# POWER_GEN.net
KiCad netlist of a schematic drawn in Altium Designer
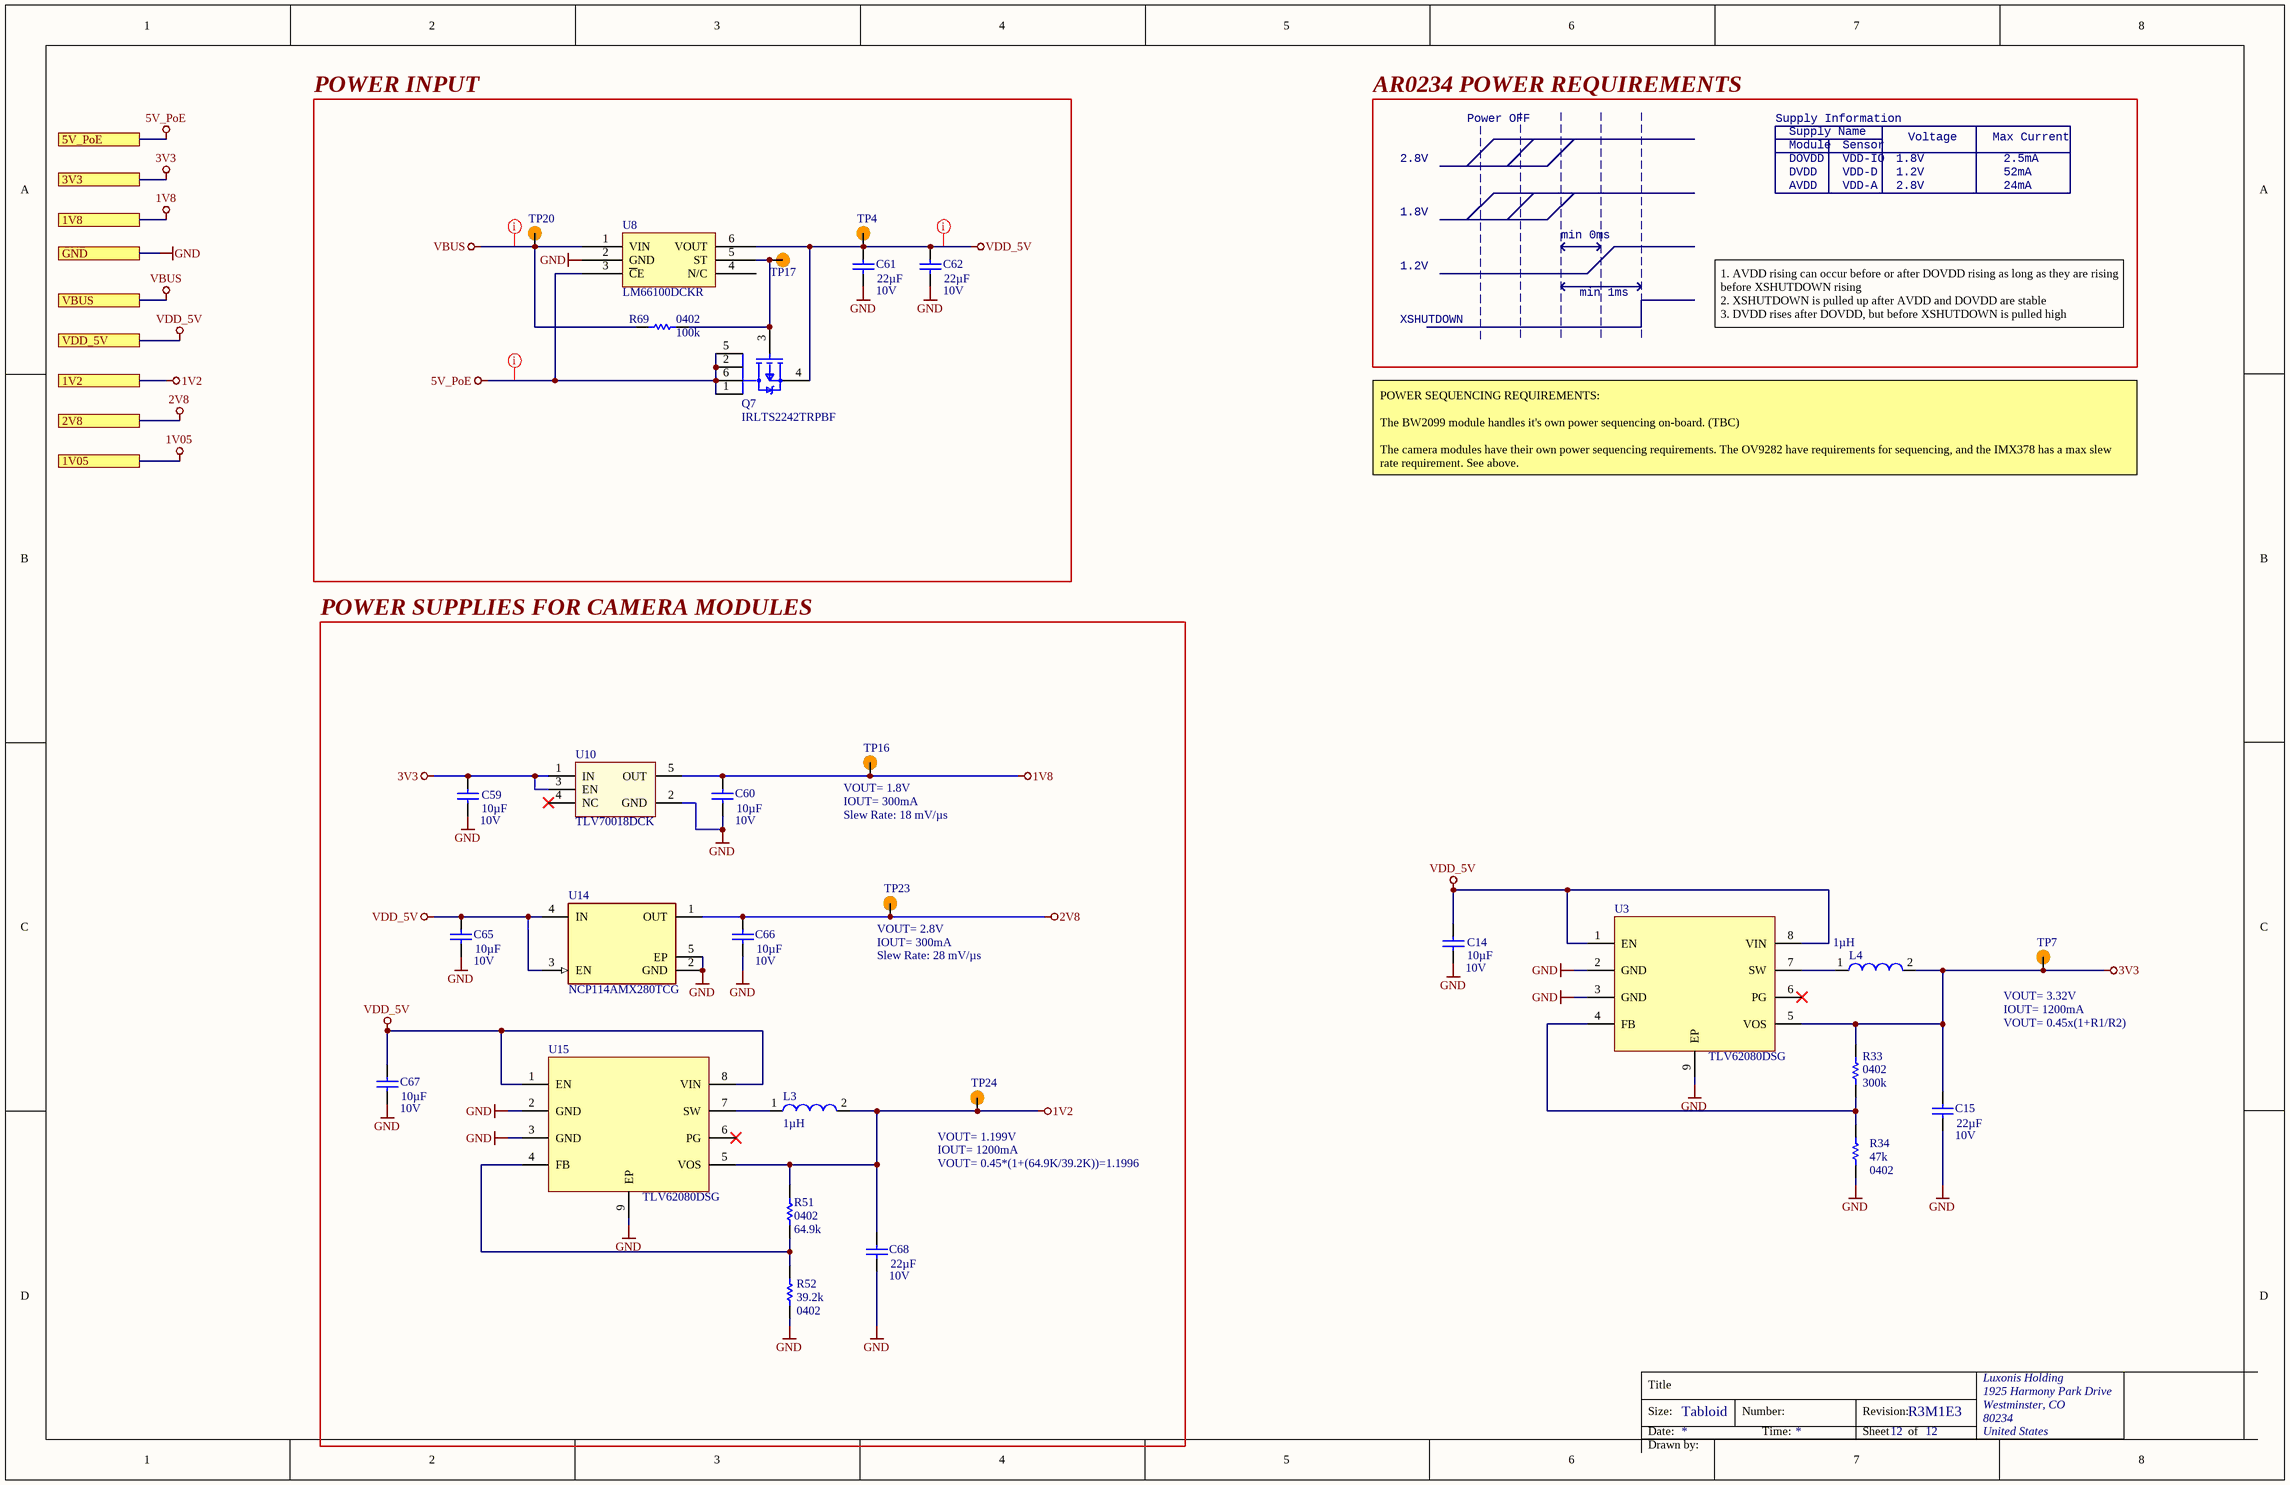
[diagram p0: POWER_GEN.SchDoc]

(export (version "E")
  (design (tool "Eeschema 10.0.6"))
  (components
    (comp (ref "C14")
      (value "10µF")
      (footprint "CAPC0603(1608)100_L")
      (description "CAP CER 10UF 10V X5R 0603 20%")
      (fields
        (field (name "TOLERANCE") "20%")
        (field (name "VOLTAGE RATING") "10V")
        (field (name "Comment") "GRM188R61A106ME69D")
      )
      (libsource (lib "Luxonis LLC") (part "LLL153C70G474ME17E"))
    )
    (comp (ref "C15")
      (value "22µF")
      (footprint "CAPC0603(1608)100_L")
      (description "CAP CER 22UF 10V X5R 0603 20%")
      (fields
        (field (name "TOLERANCE") "20%")
        (field (name "VOLTAGE RATING") "10V")
        (field (name "Comment") "GRM188R61A226ME15D")
      )
      (libsource (lib "Luxonis LLC") (part "GRM188R61C475KAAJD"))
    )
    (comp (ref "C59")
      (value "10µF")
      (footprint "CAPC0603(1608)100_L")
      (description "CAP CER 10UF 10V X5R 0603 20%")
      (fields
        (field (name "TOLERANCE") "20%")
        (field (name "VOLTAGE RATING") "10V")
        (field (name "Comment") "GRM188R61A106ME69D")
      )
      (libsource (lib "Luxonis LLC") (part "LLL153C70G474ME17E"))
    )
    (comp (ref "C60")
      (value "10µF")
      (footprint "CAPC0603(1608)100_L")
      (description "CAP CER 10UF 10V X5R 0603 20%")
      (fields
        (field (name "TOLERANCE") "20%")
        (field (name "VOLTAGE RATING") "10V")
        (field (name "Comment") "GRM188R61A106ME69D")
      )
      (libsource (lib "Luxonis LLC") (part "LLL153C70G474ME17E"))
    )
    (comp (ref "C61")
      (value "22µF")
      (footprint "CAPC0603(1608)100_L")
      (description "CAP CER 22UF 10V X5R 0603 20%")
      (fields
        (field (name "TOLERANCE") "20%")
        (field (name "VOLTAGE RATING") "10V")
        (field (name "Comment") "GRM188R61A226ME15D")
      )
      (libsource (lib "Luxonis LLC") (part "GRM188R61C475KAAJD"))
    )
    (comp (ref "C62")
      (value "22µF")
      (footprint "CAPC0603(1608)100_L")
      (description "CAP CER 22UF 10V X5R 0603 20%")
      (fields
        (field (name "TOLERANCE") "20%")
        (field (name "VOLTAGE RATING") "10V")
        (field (name "Comment") "GRM188R61A226ME15D")
      )
      (libsource (lib "Luxonis LLC") (part "GRM188R61C475KAAJD"))
    )
    (comp (ref "C65")
      (value "10µF")
      (footprint "CAPC0603(1608)100_L")
      (description "CAP CER 10UF 10V X5R 0603 20%")
      (fields
        (field (name "TOLERANCE") "20%")
        (field (name "VOLTAGE RATING") "10V")
        (field (name "Comment") "GRM188R61A106ME69D")
      )
      (libsource (lib "Luxonis LLC") (part "LLL153C70G474ME17E"))
    )
    (comp (ref "C66")
      (value "10µF")
      (footprint "CAPC0603(1608)100_L")
      (description "CAP CER 10UF 10V X5R 0603 20%")
      (fields
        (field (name "TOLERANCE") "20%")
        (field (name "VOLTAGE RATING") "10V")
        (field (name "Comment") "GRM188R61A106ME69D")
      )
      (libsource (lib "Luxonis LLC") (part "LLL153C70G474ME17E"))
    )
    (comp (ref "C67")
      (value "10µF")
      (footprint "CAPC0603(1608)100_L")
      (description "CAP CER 10UF 10V X5R 0603 20%")
      (fields
        (field (name "TOLERANCE") "20%")
        (field (name "VOLTAGE RATING") "10V")
        (field (name "Comment") "GRM188R61A106ME69D")
      )
      (libsource (lib "Luxonis LLC") (part "LLL153C70G474ME17E"))
    )
    (comp (ref "C68")
      (value "22µF")
      (footprint "CAPC0603(1608)100_L")
      (description "CAP CER 22UF 10V X5R 0603 20%")
      (fields
        (field (name "TOLERANCE") "20%")
        (field (name "VOLTAGE RATING") "10V")
        (field (name "Comment") "GRM188R61A226ME15D")
      )
      (libsource (lib "Luxonis LLC") (part "GRM188R61C475KAAJD"))
    )
    (comp (ref "L3")
      (value "1µH")
      (footprint "DFE252012P-1R0M=P2")
      (description "FIXED IND 1UH 3.2A 42 MOHM SMD")
      (fields
        (field (name "MANUFACTURER") "Murata")
        (field (name "MANUFACTURER PART NUMBER") "DFE252012P-1R0M=P2")
      )
      (libsource (lib "Luxonis LLC") (part "DFE252012P-1R0M=P2"))
    )
    (comp (ref "L4")
      (value "1µH")
      (footprint "DFE252012P-1R0M=P2")
      (description "FIXED IND 1UH 3.2A 42 MOHM SMD")
      (fields
        (field (name "MANUFACTURER") "Murata")
        (field (name "MANUFACTURER PART NUMBER") "DFE252012P-1R0M=P2")
      )
      (libsource (lib "Luxonis LLC") (part "DFE252012P-1R0M=P2"))
    )
    (comp (ref "Q7")
      (value "IRLTS2242TRPBF")
      (footprint "TSOP-6-MFG")
      (description "MOSFET P-CH 20V 6.9A 6TSOP")
      (libsource (lib "Luxonis LLC") (part "IRLTS2242TRPBF"))
    )
    (comp (ref "R33")
      (value "300k")
      (footprint "RESC0402(1005)_L")
      (description "RES SMD 300K OHM 1% 1/16W 0402")
      (fields
        (field (name "CASE/PACKAGE") "0402")
        (field (name "TOLERANCE") "1%")
        (field (name "Comment") "RC0402FR-07300KL")
      )
      (libsource (lib "Luxonis LLC") (part "Default resistor symbol"))
    )
    (comp (ref "R34")
      (value "47k")
      (footprint "RESC0402(1005)_L")
      (description "RES SMD 47K OHM 1% 1/16W 0402")
      (fields
        (field (name "CASE/PACKAGE") "0402")
        (field (name "TOLERANCE") "1%")
        (field (name "Comment") "RC0402FR-0747KL")
      )
      (libsource (lib "Luxonis LLC") (part "Default resistor symbol"))
    )
    (comp (ref "R51")
      (value "64.9k")
      (footprint "RESC0402(1005)_L")
      (description "RES SMD 64.9K OHM 1% 0.1W 0402")
      (fields
        (field (name "CASE/PACKAGE") "0402")
        (field (name "TOLERANCE") "1%")
        (field (name "Comment") "ERJ-2RKF6492X")
      )
      (libsource (lib "Luxonis LLC") (part "Default resistor symbol"))
    )
    (comp (ref "R52")
      (value "39.2k")
      (footprint "RESC0402(1005)_L")
      (description "RES SMD 39.2K OHM 1% 1/16W 0402")
      (fields
        (field (name "CASE/PACKAGE") "0402")
        (field (name "TOLERANCE") "1%")
        (field (name "Comment") "CRCW040239K2FKED")
      )
      (libsource (lib "Luxonis LLC") (part "Default resistor symbol"))
    )
    (comp (ref "R69")
      (value "100k")
      (footprint "RESC0402(1005)_L")
      (description "RES SMD 100K OHM 1% 1/16W 0402")
      (fields
        (field (name "CASE/PACKAGE") "0402")
        (field (name "TOLERANCE") "1%")
        (field (name "Comment") "RC0402FR-07100KL")
      )
      (libsource (lib "Luxonis LLC") (part "Default resistor symbol"))
    )
    (comp (ref "TP4")
      (value "TEST_POINT")
      (footprint "TP100_200_NS")
      (libsource (lib "Luxonis LLC") (part "TEST_POINT"))
    )
    (comp (ref "TP7")
      (value "TEST_POINT")
      (footprint "TP100_200_NS")
      (libsource (lib "Luxonis LLC") (part "TEST_POINT"))
    )
    (comp (ref "TP16")
      (value "TEST_POINT")
      (footprint "TP100_200_NS")
      (libsource (lib "Luxonis LLC") (part "TEST_POINT"))
    )
    (comp (ref "TP17")
      (value "TEST_POINT")
      (footprint "TP100_200_NS")
      (libsource (lib "Luxonis LLC") (part "TEST_POINT"))
    )
    (comp (ref "TP20")
      (value "TEST_POINT")
      (footprint "TP100_200_NS")
      (libsource (lib "Luxonis LLC") (part "TEST_POINT"))
    )
    (comp (ref "TP23")
      (value "TEST_POINT")
      (footprint "TP100_200_NS")
      (libsource (lib "Luxonis LLC") (part "TEST_POINT"))
    )
    (comp (ref "TP24")
      (value "TEST_POINT")
      (footprint "TP100_200_NS")
      (libsource (lib "Luxonis LLC") (part "TEST_POINT"))
    )
    (comp (ref "U3")
      (value "TLV62080DSG")
      (footprint "TLV62080DSG")
      (description "IC REG BUCK ADJ 1.2A SYNC 8WSON")
      (libsource (lib "Luxonis LLC") (part "TLV62080DSG"))
    )
    (comp (ref "U8")
      (value "LM66100DCKR")
      (footprint "LM66100DCKR")
      (description "IC OR CTRLR IDEAL DIODE SC70-6")
      (libsource (lib "Luxonis LLC") (part "LM66100DCKR"))
    )
    (comp (ref "U10")
      (value "TLV70018DCK")
      (footprint "TLV70018DCK")
      (description "IC REG LINEAR 1.8V 200MA SC70-5 Linear Voltage Regulator IC  1 Output  200mA SC-70-5")
      (libsource (lib "Luxonis LLC") (part "TLV70018DCK"))
    )
    (comp (ref "U14")
      (value "NCP114AMX280TCG")
      (footprint "FP-517CU-MFG")
      (description "Fixed Positive LDO Regulator, 2.8V, 0.23V Dropout, CMOS, PDSO4")
      (libsource (lib "Luxonis LLC") (part "d482fde4c46c8d3b68fd86b21119a5c"))
    )
    (comp (ref "U15")
      (value "TLV62080DSG")
      (footprint "TLV62080DSG")
      (description "IC REG BUCK ADJ 1.2A SYNC 8WSON")
      (libsource (lib "Luxonis LLC") (part "TLV62080DSG"))
    )
  )
  (nets
    (net (code "1") (name "1V2") (class "Default")
      (node (ref "C68") (pin "2") (pinfunction "2_2") (pintype "passive"))
      (node (ref "L3") (pin "2") (pinfunction "2_2") (pintype "passive"))
      (node (ref "R51") (pin "2") (pinfunction "2_2") (pintype "passive"))
      (node (ref "TP24") (pin "1") (pintype "passive"))
      (node (ref "U15") (pin "5") (pinfunction "VOS_5") (pintype "passive"))
    )
    (net (code "3") (name "1V8") (class "Default")
      (node (ref "C60") (pin "2") (pinfunction "2_2") (pintype "passive"))
      (node (ref "TP16") (pin "1") (pintype "passive"))
      (node (ref "U10") (pin "5") (pinfunction "OUT_5") (pintype "passive"))
    )
    (net (code "4") (name "2V8") (class "Default")
      (node (ref "C66") (pin "2") (pinfunction "2_2") (pintype "passive"))
      (node (ref "TP23") (pin "1") (pintype "passive"))
      (node (ref "U14") (pin "1") (pinfunction "OUT_1") (pintype "power_in"))
    )
    (net (code "5") (name "3V3") (class "Default")
      (node (ref "C15") (pin "2") (pinfunction "2_2") (pintype "passive"))
      (node (ref "C59") (pin "2") (pinfunction "2_2") (pintype "passive"))
      (node (ref "L4") (pin "2") (pinfunction "2_2") (pintype "passive"))
      (node (ref "R33") (pin "2") (pinfunction "2_2") (pintype "passive"))
      (node (ref "TP7") (pin "1") (pintype "passive"))
      (node (ref "U10") (pin "1") (pinfunction "IN_1") (pintype "passive"))
      (node (ref "U10") (pin "3") (pinfunction "EN_3") (pintype "passive"))
      (node (ref "U3") (pin "5") (pinfunction "VOS_5") (pintype "passive"))
    )
    (net (code "6") (name "5V_PoE") (class "Default")
      (node (ref "Q7") (pin "1") (pinfunction "D_1") (pintype "passive"))
      (node (ref "Q7") (pin "2") (pinfunction "D_2") (pintype "passive"))
      (node (ref "Q7") (pin "5") (pinfunction "D_5") (pintype "passive"))
      (node (ref "Q7") (pin "6") (pinfunction "D_6") (pintype "passive"))
      (node (ref "U8") (pin "3") (pinfunction "~{C}E_3") (pintype "passive"))
    )
    (net (code "7") (name "GND") (class "Default")
      (node (ref "C14") (pin "1") (pinfunction "1_1") (pintype "passive"))
      (node (ref "C15") (pin "1") (pinfunction "1_1") (pintype "passive"))
      (node (ref "C59") (pin "1") (pinfunction "1_1") (pintype "passive"))
      (node (ref "C60") (pin "1") (pinfunction "1_1") (pintype "passive"))
      (node (ref "C61") (pin "2") (pinfunction "2_2") (pintype "passive"))
      (node (ref "C62") (pin "2") (pinfunction "2_2") (pintype "passive"))
      (node (ref "C65") (pin "1") (pinfunction "1_1") (pintype "passive"))
      (node (ref "C66") (pin "1") (pinfunction "1_1") (pintype "passive"))
      (node (ref "C67") (pin "1") (pinfunction "1_1") (pintype "passive"))
      (node (ref "C68") (pin "1") (pinfunction "1_1") (pintype "passive"))
      (node (ref "R34") (pin "1") (pinfunction "1_1") (pintype "passive"))
      (node (ref "R52") (pin "1") (pinfunction "1_1") (pintype "passive"))
      (node (ref "U10") (pin "2") (pinfunction "GND_2") (pintype "passive"))
      (node (ref "U14") (pin "2") (pinfunction "GND_2") (pintype "power_in"))
      (node (ref "U14") (pin "5") (pinfunction "EP_5") (pintype "power_in"))
      (node (ref "U15") (pin "2") (pinfunction "GND_2") (pintype "passive"))
      (node (ref "U15") (pin "3") (pinfunction "GND_3") (pintype "passive"))
      (node (ref "U15") (pin "9") (pinfunction "EP_9") (pintype "passive"))
      (node (ref "U3") (pin "2") (pinfunction "GND_2") (pintype "passive"))
      (node (ref "U3") (pin "3") (pinfunction "GND_3") (pintype "passive"))
      (node (ref "U3") (pin "9") (pinfunction "EP_9") (pintype "passive"))
      (node (ref "U8") (pin "2") (pinfunction "GND_2") (pintype "passive"))
    )
    (net (code "8") (name "Net-(Q7-G)") (class "Default")
      (node (ref "Q7") (pin "3") (pinfunction "G_3") (pintype "passive"))
      (node (ref "R69") (pin "1") (pinfunction "1_1") (pintype "passive"))
      (node (ref "TP17") (pin "1") (pintype "passive"))
      (node (ref "U8") (pin "5") (pinfunction "ST_5") (pintype "passive"))
    )
    (net (code "9") (name "Net-(U3-FB)") (class "Default")
      (node (ref "R33") (pin "1") (pinfunction "1_1") (pintype "passive"))
      (node (ref "R34") (pin "2") (pinfunction "2_2") (pintype "passive"))
      (node (ref "U3") (pin "4") (pinfunction "FB_4") (pintype "passive"))
    )
    (net (code "10") (name "Net-(U3-SW)") (class "Default")
      (node (ref "L4") (pin "1") (pinfunction "1_1") (pintype "passive"))
      (node (ref "U3") (pin "7") (pinfunction "SW_7") (pintype "passive"))
    )
    (net (code "11") (name "Net-(U15-FB)") (class "Default")
      (node (ref "R51") (pin "1") (pinfunction "1_1") (pintype "passive"))
      (node (ref "R52") (pin "2") (pinfunction "2_2") (pintype "passive"))
      (node (ref "U15") (pin "4") (pinfunction "FB_4") (pintype "passive"))
    )
    (net (code "12") (name "Net-(U15-SW)") (class "Default")
      (node (ref "L3") (pin "1") (pinfunction "1_1") (pintype "passive"))
      (node (ref "U15") (pin "7") (pinfunction "SW_7") (pintype "passive"))
    )
    (net (code "13") (name "VBUS") (class "Default")
      (node (ref "R69") (pin "2") (pinfunction "2_2") (pintype "passive"))
      (node (ref "TP20") (pin "1") (pintype "passive"))
      (node (ref "U8") (pin "1") (pinfunction "VIN_1") (pintype "passive"))
    )
    (net (code "14") (name "VDD_5V") (class "Default")
      (node (ref "C14") (pin "2") (pinfunction "2_2") (pintype "passive"))
      (node (ref "C61") (pin "1") (pinfunction "1_1") (pintype "passive"))
      (node (ref "C62") (pin "1") (pinfunction "1_1") (pintype "passive"))
      (node (ref "C65") (pin "2") (pinfunction "2_2") (pintype "passive"))
      (node (ref "C67") (pin "2") (pinfunction "2_2") (pintype "passive"))
      (node (ref "Q7") (pin "4") (pinfunction "S_4") (pintype "passive"))
      (node (ref "TP4") (pin "1") (pintype "passive"))
      (node (ref "U14") (pin "3") (pinfunction "EN_3") (pintype "input"))
      (node (ref "U14") (pin "4") (pinfunction "IN_4") (pintype "power_in"))
      (node (ref "U15") (pin "1") (pinfunction "EN_1") (pintype "passive"))
      (node (ref "U15") (pin "8") (pinfunction "VIN_8") (pintype "passive"))
      (node (ref "U3") (pin "1") (pinfunction "EN_1") (pintype "passive"))
      (node (ref "U3") (pin "8") (pinfunction "VIN_8") (pintype "passive"))
      (node (ref "U8") (pin "6") (pinfunction "VOUT_6") (pintype "passive"))
    )
    (net (code "15") (name "unconnected-(U3-PG-Pad6)") (class "Default")
      (node (ref "U3") (pin "6") (pinfunction "PG_6") (pintype "passive+no_connect"))
    )
    (net (code "16") (name "unconnected-(U8-N{slash}C-Pad4)") (class "Default")
      (node (ref "U8") (pin "4") (pinfunction "N/C_4") (pintype "passive"))
    )
    (net (code "17") (name "unconnected-(U10-NC-Pad4)") (class "Default")
      (node (ref "U10") (pin "4") (pinfunction "NC_4") (pintype "passive+no_connect"))
    )
    (net (code "18") (name "unconnected-(U15-PG-Pad6)") (class "Default")
      (node (ref "U15") (pin "6") (pinfunction "PG_6") (pintype "passive+no_connect"))
    )
  )
)
